# Shutdown_2019_v1_1_9.net
KiCad netlist of a schematic drawn in Altium Designer
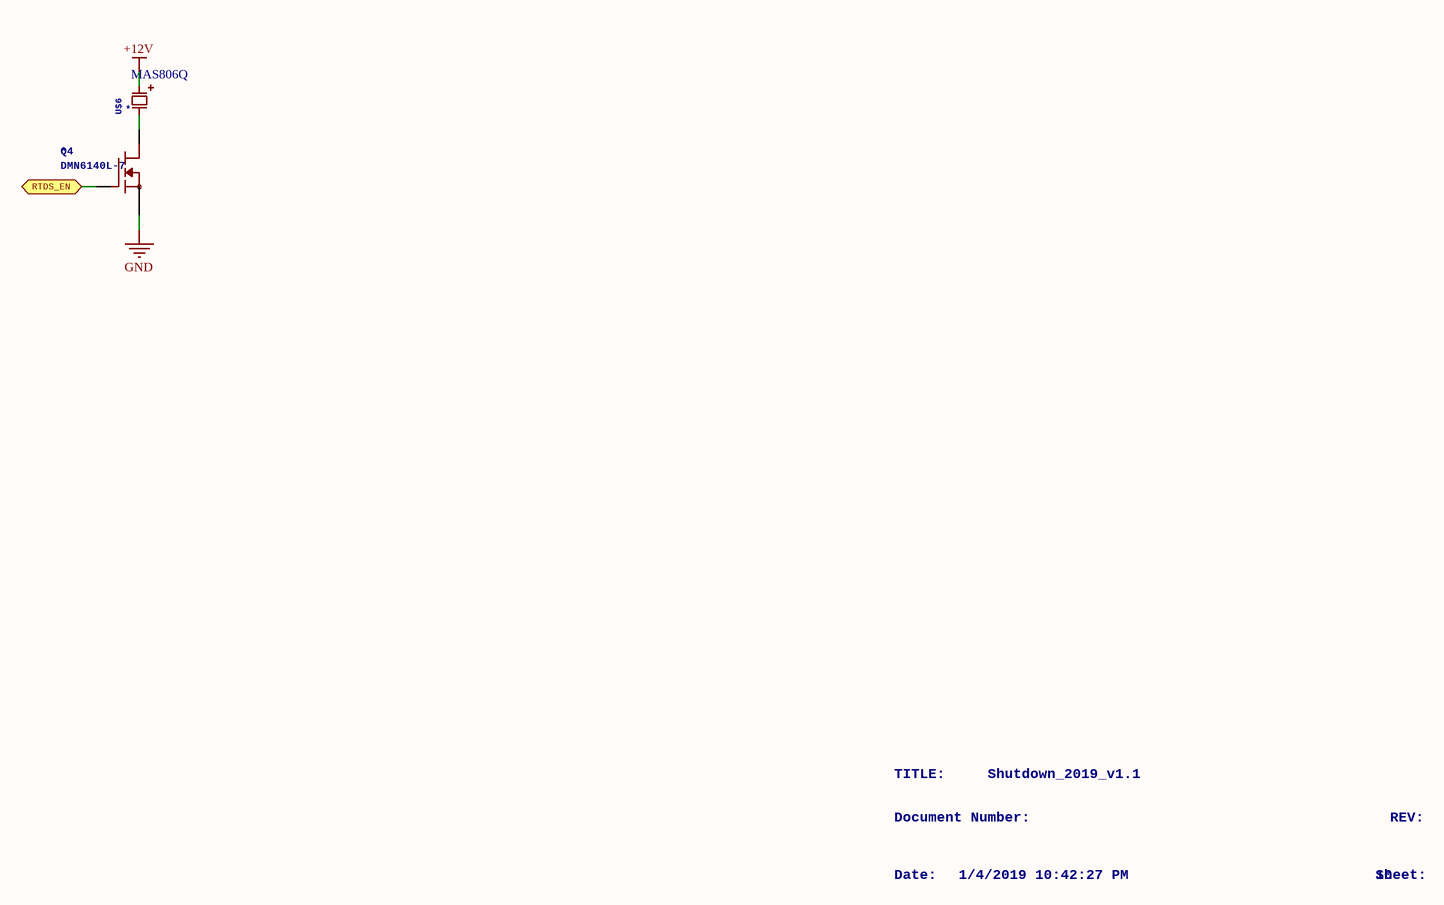
[diagram p0: Shutdown_2019_v1.1_9.SchDoc]

(export (version "E")
  (design (tool "Eeschema 10.0.6"))
  (components
    (comp (ref "Q4")
      (value "DMN6140L-7")
      (footprint "SOT23")
      (description "DMN6140L-7 Vgs(th) = 3V, Rds(on) = 140mOhm, Vds(max) = 60V")
      (fields (field (name "NAME") "*"))
      (libsource (lib "TRANS") (part "DMN6140L-7"))
    )
    (comp (ref "U$6")
      (value "MAS806Q")
      (footprint "MAS806Q")
      (description "Mallory MAS806Q  PiezoElectric Buzzer  6-14V -- 103dB -- 50mA buzzerDatasheet")
      (fields (field (name "NAME") "*"))
      (libsource (lib "MALLORY") (part "MAS806Q"))
    )
  )
  (nets
    (net (code "1") (name "+12V") (class "Default")
      (node (ref "U$6") (pin "POS") (pinfunction "A_POS") (pintype "passive"))
    )
    (net (code "2") (name "/RTDS_EN") (class "Default")
      (node (ref "Q4") (pin "1") (pinfunction "G_1") (pintype "passive"))
    )
    (net (code "3") (name "GND") (class "Default")
      (node (ref "Q4") (pin "2") (pinfunction "S_2") (pintype "passive"))
    )
    (net (code "4") (name "Net-(Q4-D)") (class "Default")
      (node (ref "Q4") (pin "3") (pinfunction "D_3") (pintype "passive"))
      (node (ref "U$6") (pin "NEG") (pinfunction "B_NEG") (pintype "output"))
    )
  )
)
